# A7000RiscPC_Joystick.net
KiCad netlist of a schematic drawn in Altium Designer
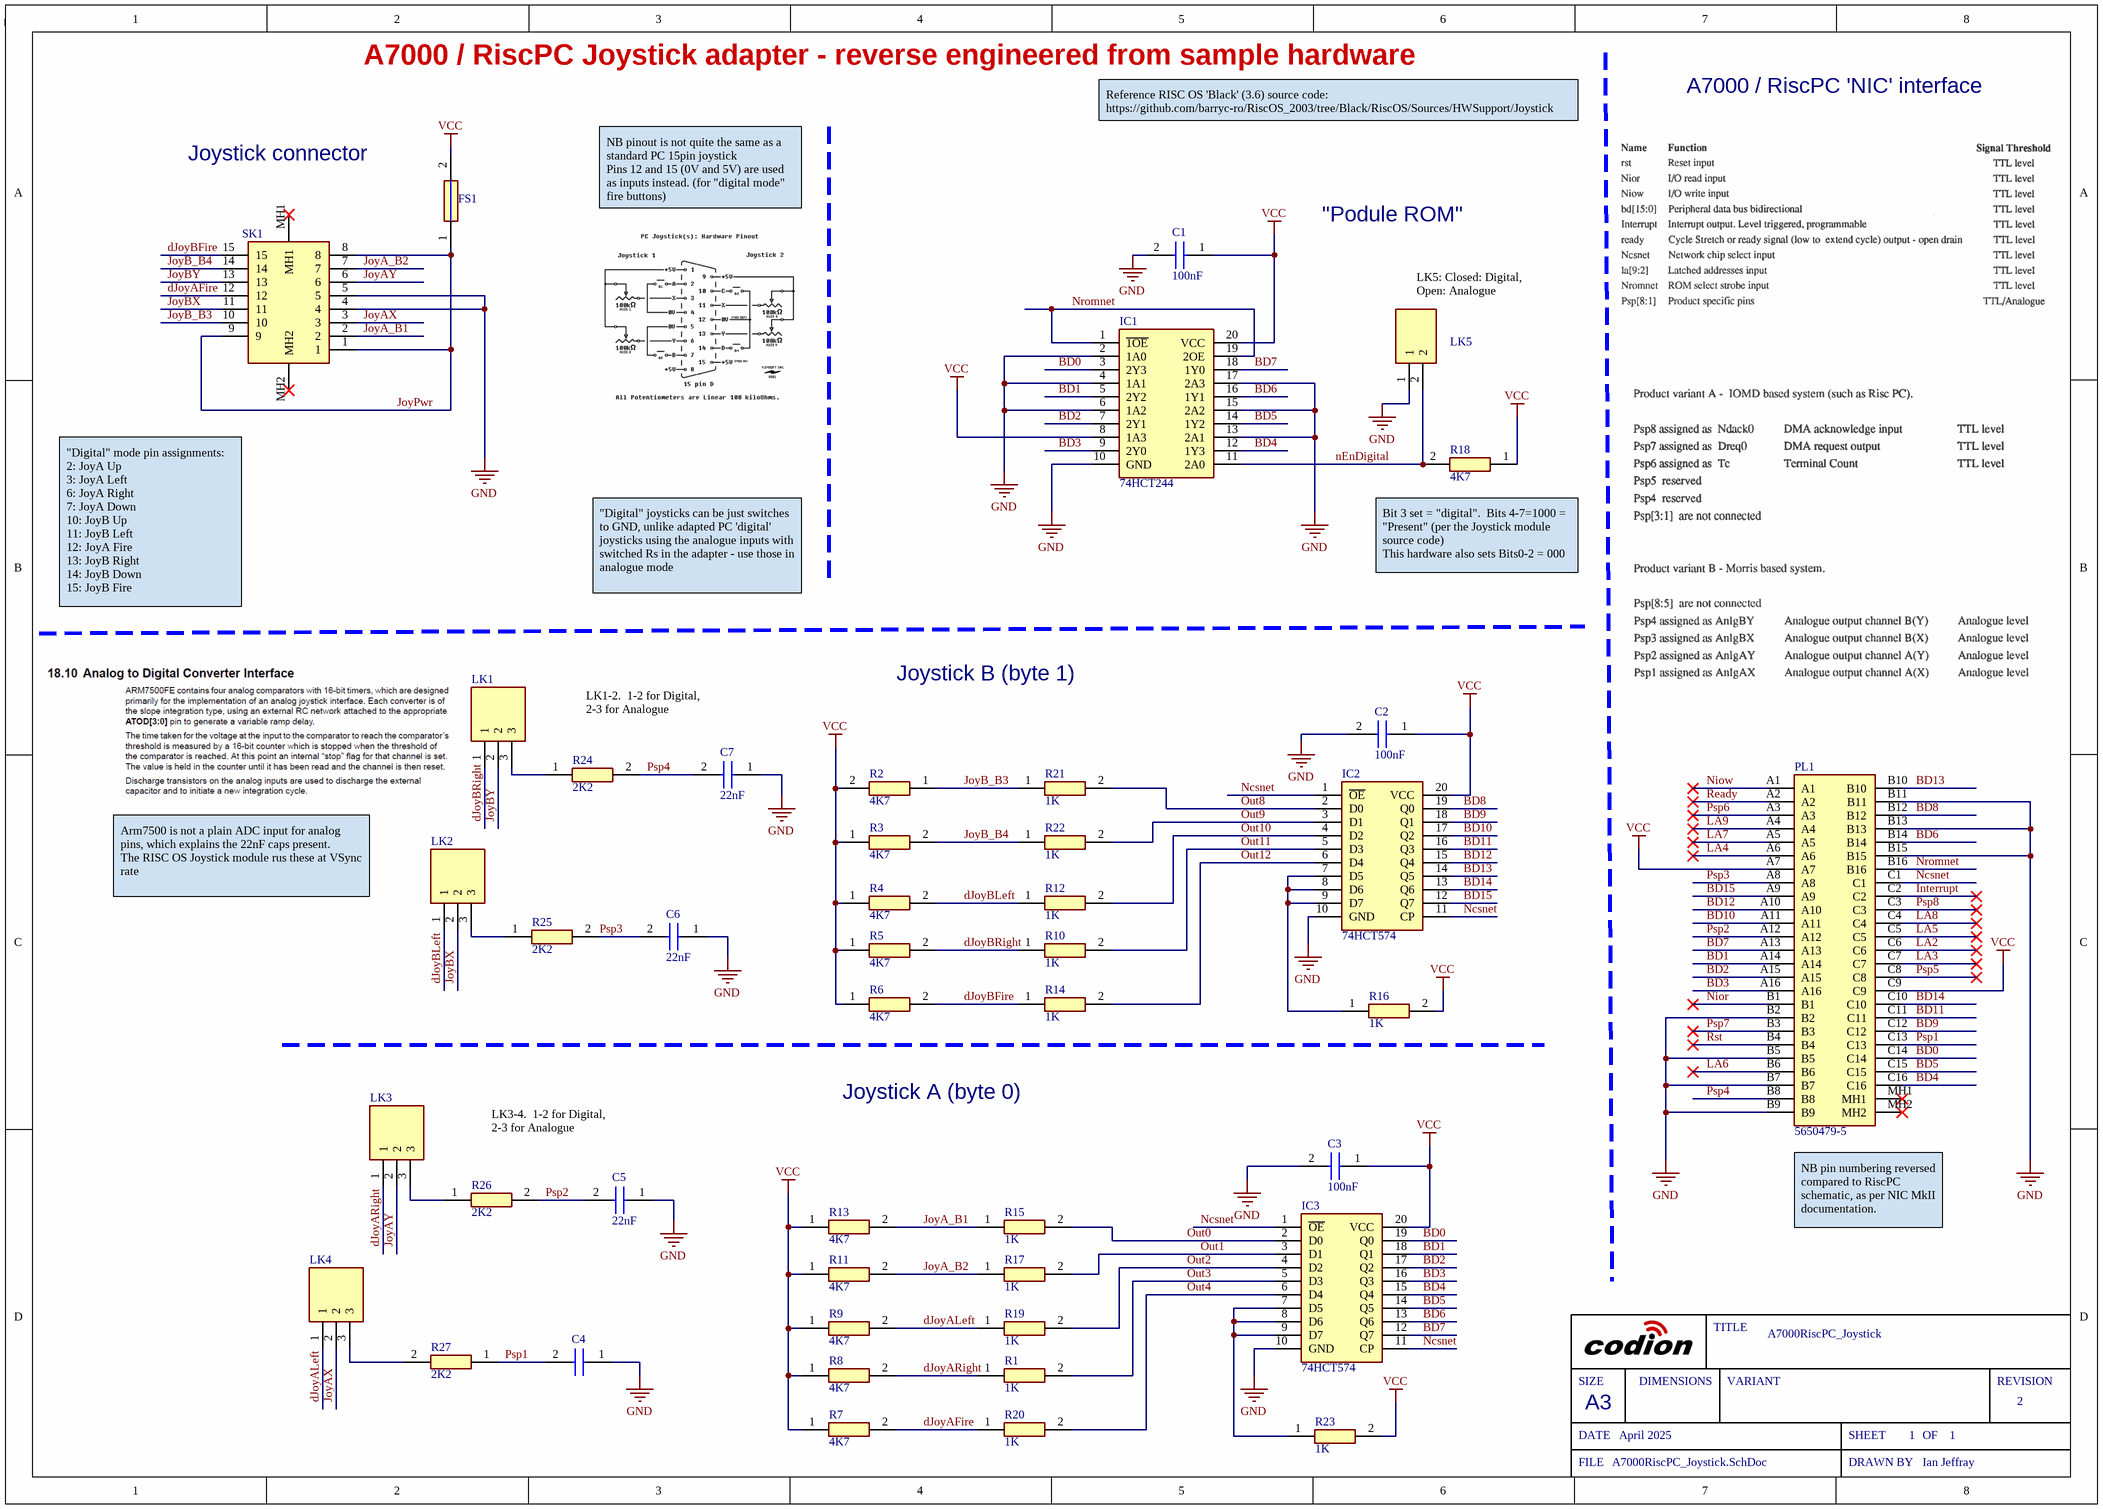
[diagram p0: A7000RiscPC_Joystick.SchDoc]

(export (version "E")
  (design (tool "Eeschema 10.0.6"))
  (components
    (comp (ref "C1")
      (value "100nF")
      (footprint "SamacSys:CAPC1608X90N")
      (description "Capacitor")
      (fields
        (field (name "MANUFACTURER_PART_NUMBER") "06033C104KAT4A")
        (field (name "MOUSER PART NUMBER") "581-06033C104KAT4A")
      )
      (libsource (lib "SamacSys") (part "06033C104KAT4A"))
    )
    (comp (ref "C2")
      (value "100nF")
      (footprint "SamacSys:CAPC1608X90N")
      (description "Capacitor")
      (fields
        (field (name "MANUFACTURER_PART_NUMBER") "06033C104KAT4A")
        (field (name "MOUSER PART NUMBER") "581-06033C104KAT4A")
      )
      (libsource (lib "SamacSys") (part "06033C104KAT4A"))
    )
    (comp (ref "C3")
      (value "100nF")
      (footprint "SamacSys:CAPC1608X90N")
      (description "Capacitor")
      (fields
        (field (name "MANUFACTURER_PART_NUMBER") "06033C104KAT4A")
        (field (name "MOUSER PART NUMBER") "581-06033C104KAT4A")
      )
      (libsource (lib "SamacSys") (part "06033C104KAT4A"))
    )
    (comp (ref "C4")
      (value "06033C104KAT4A")
      (footprint "SamacSys:CAPC1608X90N")
      (description "Capacitor")
      (fields (field (name "MOUSER PART NUMBER") "581-06033C104KAT4A"))
      (libsource (lib "SamacSys") (part "06033C104KAT4A"))
    )
    (comp (ref "C5")
      (value "22nF")
      (footprint "SamacSys:CAPC1608X90N")
      (description "Capacitor")
      (fields
        (field (name "MANUFACTURER_PART_NUMBER") "06035C223JAT2A")
        (field (name "MOUSER PART NUMBER") "581-06035C223JAT2A")
      )
      (libsource (lib "*") (part "06035C223JAT2A"))
    )
    (comp (ref "C6")
      (value "22nF")
      (footprint "SamacSys:CAPC1608X90N")
      (description "Capacitor")
      (fields
        (field (name "MANUFACTURER_PART_NUMBER") "06035C223JAT2A")
        (field (name "MOUSER PART NUMBER") "581-06035C223JAT2A")
      )
      (libsource (lib "*") (part "06035C223JAT2A"))
    )
    (comp (ref "C7")
      (value "22nF")
      (footprint "SamacSys:CAPC1608X90N")
      (description "Capacitor")
      (fields
        (field (name "MANUFACTURER_PART_NUMBER") "06035C223JAT2A")
        (field (name "MOUSER PART NUMBER") "581-06035C223JAT2A")
      )
      (libsource (lib "*") (part "06035C223JAT2A"))
    )
    (comp (ref "FS1")
      (value "0679L0250-05")
      (footprint "SamacSys:FUSC6125X279N")
      (description "Fuse")
      (fields (field (name "MOUSER PART NUMBER") "530-0679L0250-05"))
      (libsource (lib "*") (part "0679L0250-05"))
    )
    (comp (ref "IC1")
      (value "74HCT244")
      (footprint "SamacSys:SOIC127P1030X265-20N")
      (description "Integrated Circuit")
      (fields
        (field (name "MANUFACTURER_PART_NUMBER") "CD74HCT244M")
        (field (name "MOUSER PART NUMBER") "595-CD74HCT244M")
      )
      (libsource (lib "*") (part "CD74HCT244M"))
    )
    (comp (ref "IC2")
      (value "74HCT574")
      (footprint "SamacSys:SOIC127P1030X265-20N")
      (description "Integrated Circuit")
      (fields
        (field (name "MANUFACTURER_PART_NUMBER") "CD74HCT574M")
        (field (name "MOUSER PART NUMBER") "595-CD74HCT574M")
      )
      (libsource (lib "*") (part "CD74HCT574M"))
    )
    (comp (ref "IC3")
      (value "74HCT574")
      (footprint "SamacSys:SOIC127P1030X265-20N")
      (description "Integrated Circuit")
      (fields
        (field (name "MANUFACTURER_PART_NUMBER") "CD74HCT574M")
        (field (name "MOUSER PART NUMBER") "595-CD74HCT574M")
      )
      (libsource (lib "*") (part "CD74HCT574M"))
    )
    (comp (ref "LK1")
      (value "PREC003SAAN-RC")
      (footprint "SamacSys:HDRV3W64P0X254_1X3_762X254X868P")
      (description "Connector")
      (libsource (lib "*") (part "PREC003SAAN-RC"))
    )
    (comp (ref "LK2")
      (value "PREC003SAAN-RC")
      (footprint "SamacSys:HDRV3W64P0X254_1X3_762X254X868P")
      (description "Connector")
      (libsource (lib "*") (part "PREC003SAAN-RC"))
    )
    (comp (ref "LK3")
      (value "PREC003SAAN-RC")
      (footprint "SamacSys:HDRV3W64P0X254_1X3_762X254X868P")
      (description "Connector")
      (libsource (lib "*") (part "PREC003SAAN-RC"))
    )
    (comp (ref "LK4")
      (value "PREC003SAAN-RC")
      (footprint "SamacSys:HDRV3W64P0X254_1X3_762X254X868P")
      (description "Connector")
      (libsource (lib "*") (part "PREC003SAAN-RC"))
    )
    (comp (ref "LK5")
      (value "PREC002SAAN-RC")
      (footprint "SamacSys:HDRV2W64P0X254_1X2_508X254X854P")
      (description "Connector")
      (libsource (lib "*") (part "PREC002SAAN-RC"))
    )
    (comp (ref "PL1")
      (value "5650479-5")
      (footprint "SamacSys:56504795")
      (description "Connector")
      (fields (field (name "MOUSER PART NUMBER") "571-5650479-5"))
      (libsource (lib "*") (part "5650479-5"))
    )
    (comp (ref "R1")
      (value "1K")
      (footprint "SamacSys:RESC1005X35N")
      (description "Resistor")
      (fields
        (field (name "MANUFACTURER_PART_NUMBER") "CPF0402B102KE1")
        (field (name "MOUSER PART NUMBER") "279-CPF0402B102KE1")
      )
      (libsource (lib "*") (part "CPF0402B102KE1"))
    )
    (comp (ref "R2")
      (value "4K7")
      (footprint "SamacSys:RESC1005X35N")
      (description "Resistor")
      (fields
        (field (name "MANUFACTURER_PART_NUMBER") "CPF0402B4K7E")
        (field (name "MOUSER PART NUMBER") "279-CPF0402B4K7E")
      )
      (libsource (lib "") (part "CPF0402B4K7E_1"))
    )
    (comp (ref "R3")
      (value "4K7")
      (footprint "SamacSys:RESC1005X35N")
      (description "Resistor")
      (fields
        (field (name "MANUFACTURER_PART_NUMBER") "CPF0402B4K7E")
        (field (name "MOUSER PART NUMBER") "279-CPF0402B4K7E")
      )
      (libsource (lib "*") (part "CPF0402B4K7E"))
    )
    (comp (ref "R4")
      (value "4K7")
      (footprint "SamacSys:RESC1005X35N")
      (description "Resistor")
      (fields
        (field (name "MANUFACTURER_PART_NUMBER") "CPF0402B4K7E")
        (field (name "MOUSER PART NUMBER") "279-CPF0402B4K7E")
      )
      (libsource (lib "*") (part "CPF0402B4K7E"))
    )
    (comp (ref "R5")
      (value "4K7")
      (footprint "SamacSys:RESC1005X35N")
      (description "Resistor")
      (fields
        (field (name "MANUFACTURER_PART_NUMBER") "CPF0402B4K7E")
        (field (name "MOUSER PART NUMBER") "279-CPF0402B4K7E")
      )
      (libsource (lib "*") (part "CPF0402B4K7E"))
    )
    (comp (ref "R6")
      (value "4K7")
      (footprint "SamacSys:RESC1005X35N")
      (description "Resistor")
      (fields
        (field (name "MANUFACTURER_PART_NUMBER") "CPF0402B4K7E")
        (field (name "MOUSER PART NUMBER") "279-CPF0402B4K7E")
      )
      (libsource (lib "*") (part "CPF0402B4K7E"))
    )
    (comp (ref "R7")
      (value "4K7")
      (footprint "SamacSys:RESC1005X35N")
      (description "Resistor")
      (fields
        (field (name "MANUFACTURER_PART_NUMBER") "CPF0402B4K7E")
        (field (name "MOUSER PART NUMBER") "279-CPF0402B4K7E")
      )
      (libsource (lib "*") (part "CPF0402B4K7E"))
    )
    (comp (ref "R8")
      (value "4K7")
      (footprint "SamacSys:RESC1005X35N")
      (description "Resistor")
      (fields
        (field (name "MANUFACTURER_PART_NUMBER") "CPF0402B4K7E")
        (field (name "MOUSER PART NUMBER") "279-CPF0402B4K7E")
      )
      (libsource (lib "*") (part "CPF0402B4K7E"))
    )
    (comp (ref "R9")
      (value "4K7")
      (footprint "SamacSys:RESC1005X35N")
      (description "Resistor")
      (fields
        (field (name "MANUFACTURER_PART_NUMBER") "CPF0402B4K7E")
        (field (name "MOUSER PART NUMBER") "279-CPF0402B4K7E")
      )
      (libsource (lib "*") (part "CPF0402B4K7E"))
    )
    (comp (ref "R10")
      (value "1K")
      (footprint "SamacSys:RESC1005X35N")
      (description "Resistor")
      (fields
        (field (name "MANUFACTURER_PART_NUMBER") "CPF0402B102KE1")
        (field (name "MOUSER PART NUMBER") "279-CPF0402B102KE1")
      )
      (libsource (lib "*") (part "CPF0402B102KE1"))
    )
    (comp (ref "R11")
      (value "4K7")
      (footprint "SamacSys:RESC1005X35N")
      (description "Resistor")
      (fields
        (field (name "MANUFACTURER_PART_NUMBER") "CPF0402B4K7E")
        (field (name "MOUSER PART NUMBER") "279-CPF0402B4K7E")
      )
      (libsource (lib "*") (part "CPF0402B4K7E"))
    )
    (comp (ref "R12")
      (value "1K")
      (footprint "SamacSys:RESC1005X35N")
      (description "Resistor")
      (fields
        (field (name "MANUFACTURER_PART_NUMBER") "CPF0402B102KE1")
        (field (name "MOUSER PART NUMBER") "279-CPF0402B102KE1")
      )
      (libsource (lib "*") (part "CPF0402B102KE1"))
    )
    (comp (ref "R13")
      (value "4K7")
      (footprint "SamacSys:RESC1005X35N")
      (description "Resistor")
      (fields
        (field (name "MANUFACTURER_PART_NUMBER") "CPF0402B4K7E")
        (field (name "MOUSER PART NUMBER") "279-CPF0402B4K7E")
      )
      (libsource (lib "*") (part "CPF0402B4K7E"))
    )
    (comp (ref "R14")
      (value "1K")
      (footprint "SamacSys:RESC1005X35N")
      (description "Resistor")
      (fields
        (field (name "MANUFACTURER_PART_NUMBER") "CPF0402B102KE1")
        (field (name "MOUSER PART NUMBER") "279-CPF0402B102KE1")
      )
      (libsource (lib "*") (part "CPF0402B102KE1"))
    )
    (comp (ref "R15")
      (value "1K")
      (footprint "SamacSys:RESC1005X35N")
      (description "Resistor")
      (fields
        (field (name "MANUFACTURER_PART_NUMBER") "CPF0402B102KE1")
        (field (name "MOUSER PART NUMBER") "279-CPF0402B102KE1")
      )
      (libsource (lib "*") (part "CPF0402B102KE1"))
    )
    (comp (ref "R16")
      (value "1K")
      (footprint "SamacSys:RESC1005X35N")
      (description "Resistor")
      (fields (field (name "MANUFACTURER_PART_NUMBER") "CPF0402B2K2E"))
      (libsource (lib "") (part "CPF0402B2K2E_1"))
    )
    (comp (ref "R17")
      (value "1K")
      (footprint "SamacSys:RESC1005X35N")
      (description "Resistor")
      (fields
        (field (name "MANUFACTURER_PART_NUMBER") "CPF0402B102KE1")
        (field (name "MOUSER PART NUMBER") "279-CPF0402B102KE1")
      )
      (libsource (lib "*") (part "CPF0402B102KE1"))
    )
    (comp (ref "R18")
      (value "4K7")
      (footprint "SamacSys:RESC1005X35N")
      (description "Resistor")
      (fields
        (field (name "MANUFACTURER_PART_NUMBER") "CPF0402B4K7E")
        (field (name "MOUSER PART NUMBER") "279-CPF0402B4K7E")
      )
      (libsource (lib "") (part "CPF0402B4K7E_1"))
    )
    (comp (ref "R19")
      (value "1K")
      (footprint "SamacSys:RESC1005X35N")
      (description "Resistor")
      (fields
        (field (name "MANUFACTURER_PART_NUMBER") "CPF0402B102KE1")
        (field (name "MOUSER PART NUMBER") "279-CPF0402B102KE1")
      )
      (libsource (lib "*") (part "CPF0402B102KE1"))
    )
    (comp (ref "R20")
      (value "1K")
      (footprint "SamacSys:RESC1005X35N")
      (description "Resistor")
      (fields
        (field (name "MANUFACTURER_PART_NUMBER") "CPF0402B102KE1")
        (field (name "MOUSER PART NUMBER") "279-CPF0402B102KE1")
      )
      (libsource (lib "*") (part "CPF0402B102KE1"))
    )
    (comp (ref "R21")
      (value "1K")
      (footprint "SamacSys:RESC1005X35N")
      (description "Resistor")
      (fields
        (field (name "MANUFACTURER_PART_NUMBER") "CPF0402B102KE1")
        (field (name "MOUSER PART NUMBER") "279-CPF0402B102KE1")
      )
      (libsource (lib "*") (part "CPF0402B102KE1"))
    )
    (comp (ref "R22")
      (value "1K")
      (footprint "SamacSys:RESC1005X35N")
      (description "Resistor")
      (fields
        (field (name "MANUFACTURER_PART_NUMBER") "CPF0402B102KE1")
        (field (name "MOUSER PART NUMBER") "279-CPF0402B102KE1")
      )
      (libsource (lib "*") (part "CPF0402B102KE1"))
    )
    (comp (ref "R23")
      (value "1K")
      (footprint "SamacSys:RESC1005X35N")
      (description "Resistor")
      (fields
        (field (name "MANUFACTURER_PART_NUMBER") "CPF0402B102KE1")
        (field (name "MOUSER PART NUMBER") "279-CPF0402B102KE1")
      )
      (libsource (lib "*") (part "CPF0402B102KE1"))
    )
    (comp (ref "R24")
      (value "2K2")
      (footprint "SamacSys:RESC1005X35N")
      (description "Resistor")
      (fields (field (name "MANUFACTURER_PART_NUMBER") "CPF0402B2K2E"))
      (libsource (lib "") (part "CPF0402B2K2E_1"))
    )
    (comp (ref "R25")
      (value "2K2")
      (footprint "SamacSys:RESC1005X35N")
      (description "Resistor")
      (fields (field (name "MANUFACTURER_PART_NUMBER") "CPF0402B2K2E"))
      (libsource (lib "") (part "CPF0402B2K2E_1"))
    )
    (comp (ref "R26")
      (value "2K2")
      (footprint "SamacSys:RESC1005X35N")
      (description "Resistor")
      (fields (field (name "MANUFACTURER_PART_NUMBER") "CPF0402B2K2E"))
      (libsource (lib "") (part "CPF0402B2K2E_1"))
    )
    (comp (ref "R27")
      (value "2K2")
      (footprint "SamacSys:RESC1005X35N")
      (description "Resistor")
      (fields (field (name "MANUFACTURER_PART_NUMBER") "CPF0402B2K2E"))
      (libsource (lib "*") (part "CPF0402B2K2E"))
    )
    (comp (ref "SK1")
      (value "5747845-4")
      (footprint "SamacSys:57478454")
      (description "Connector")
      (fields (field (name "MOUSER PART NUMBER") "571-5747845-4"))
      (libsource (lib "*") (part "5747845-4"))
    )
  )
  (nets
    (net (code "1") (name "/BD0") (class "Default")
      (node (ref "IC1") (pin "3") (pinfunction "2Y3_3") (pintype "passive"))
      (node (ref "IC3") (pin "19") (pinfunction "Q0_19") (pintype "passive"))
      (node (ref "PL1") (pin "C14") (pinfunction "C14_C14") (pintype "passive"))
    )
    (net (code "2") (name "/BD1") (class "Default")
      (node (ref "IC1") (pin "5") (pinfunction "2Y2_5") (pintype "passive"))
      (node (ref "IC3") (pin "18") (pinfunction "Q1_18") (pintype "passive"))
      (node (ref "PL1") (pin "A14") (pinfunction "A14_A14") (pintype "passive"))
    )
    (net (code "3") (name "/BD2") (class "Default")
      (node (ref "IC1") (pin "7") (pinfunction "2Y1_7") (pintype "passive"))
      (node (ref "IC3") (pin "17") (pinfunction "Q2_17") (pintype "passive"))
      (node (ref "PL1") (pin "A15") (pinfunction "A15_A15") (pintype "passive"))
    )
    (net (code "4") (name "/BD3") (class "Default")
      (node (ref "IC1") (pin "9") (pinfunction "2Y0_9") (pintype "passive"))
      (node (ref "IC3") (pin "16") (pinfunction "Q3_16") (pintype "passive"))
      (node (ref "PL1") (pin "A16") (pinfunction "A16_A16") (pintype "passive"))
    )
    (net (code "5") (name "/BD4") (class "Default")
      (node (ref "IC1") (pin "12") (pinfunction "1Y3_12") (pintype "passive"))
      (node (ref "IC3") (pin "15") (pinfunction "Q4_15") (pintype "passive"))
      (node (ref "PL1") (pin "C16") (pinfunction "C16_C16") (pintype "passive"))
    )
    (net (code "6") (name "/BD5") (class "Default")
      (node (ref "IC1") (pin "14") (pinfunction "1Y2_14") (pintype "passive"))
      (node (ref "IC3") (pin "14") (pinfunction "Q5_14") (pintype "passive"))
      (node (ref "PL1") (pin "C15") (pinfunction "C15_C15") (pintype "passive"))
    )
    (net (code "7") (name "/BD6") (class "Default")
      (node (ref "IC1") (pin "16") (pinfunction "1Y1_16") (pintype "passive"))
      (node (ref "IC3") (pin "13") (pinfunction "Q6_13") (pintype "passive"))
      (node (ref "PL1") (pin "B14") (pinfunction "B14_B14") (pintype "passive"))
    )
    (net (code "8") (name "/BD7") (class "Default")
      (node (ref "IC1") (pin "18") (pinfunction "1Y0_18") (pintype "passive"))
      (node (ref "IC3") (pin "12") (pinfunction "Q7_12") (pintype "passive"))
      (node (ref "PL1") (pin "A13") (pinfunction "A13_A13") (pintype "passive"))
    )
    (net (code "9") (name "/BD8") (class "Default")
      (node (ref "IC2") (pin "19") (pinfunction "Q0_19") (pintype "passive"))
      (node (ref "PL1") (pin "B12") (pinfunction "B12_B12") (pintype "passive"))
    )
    (net (code "10") (name "/BD9") (class "Default")
      (node (ref "IC2") (pin "18") (pinfunction "Q1_18") (pintype "passive"))
      (node (ref "PL1") (pin "C12") (pinfunction "C12_C12") (pintype "passive"))
    )
    (net (code "11") (name "/BD10") (class "Default")
      (node (ref "IC2") (pin "17") (pinfunction "Q2_17") (pintype "passive"))
      (node (ref "PL1") (pin "A11") (pinfunction "A11_A11") (pintype "passive"))
    )
    (net (code "12") (name "/BD11") (class "Default")
      (node (ref "IC2") (pin "16") (pinfunction "Q3_16") (pintype "passive"))
      (node (ref "PL1") (pin "C11") (pinfunction "C11_C11") (pintype "passive"))
    )
    (net (code "13") (name "/BD12") (class "Default")
      (node (ref "IC2") (pin "15") (pinfunction "Q4_15") (pintype "passive"))
      (node (ref "PL1") (pin "A10") (pinfunction "A10_A10") (pintype "passive"))
    )
    (net (code "14") (name "/BD13") (class "Default")
      (node (ref "IC2") (pin "14") (pinfunction "Q5_14") (pintype "passive"))
      (node (ref "PL1") (pin "B10") (pinfunction "B10_B10") (pintype "passive"))
    )
    (net (code "15") (name "/BD14") (class "Default")
      (node (ref "IC2") (pin "13") (pinfunction "Q6_13") (pintype "passive"))
      (node (ref "PL1") (pin "C10") (pinfunction "C10_C10") (pintype "passive"))
    )
    (net (code "16") (name "/BD15") (class "Default")
      (node (ref "IC2") (pin "12") (pinfunction "Q7_12") (pintype "passive"))
      (node (ref "PL1") (pin "A9") (pinfunction "A9_A9") (pintype "passive"))
    )
    (net (code "17") (name "/Interrupt") (class "Default")
      (node (ref "PL1") (pin "C2") (pinfunction "C2_C2") (pintype "passive+no_connect"))
    )
    (net (code "18") (name "/JoyAX") (class "Default")
      (node (ref "LK4") (pin "2") (pinfunction "2_2") (pintype "passive"))
      (node (ref "SK1") (pin "3") (pinfunction "3_3") (pintype "passive"))
    )
    (net (code "19") (name "/JoyAY") (class "Default")
      (node (ref "LK3") (pin "2") (pinfunction "2_2") (pintype "passive"))
      (node (ref "SK1") (pin "6") (pinfunction "6_6") (pintype "passive"))
    )
    (net (code "20") (name "/JoyA_B1") (class "Default")
      (node (ref "R13") (pin "2") (pinfunction "2_2") (pintype "passive"))
      (node (ref "R15") (pin "1") (pinfunction "1_1") (pintype "passive"))
      (node (ref "SK1") (pin "2") (pinfunction "2_2") (pintype "passive"))
    )
    (net (code "21") (name "/JoyA_B2") (class "Default")
      (node (ref "R11") (pin "2") (pinfunction "2_2") (pintype "passive"))
      (node (ref "R17") (pin "1") (pinfunction "1_1") (pintype "passive"))
      (node (ref "SK1") (pin "7") (pinfunction "7_7") (pintype "passive"))
    )
    (net (code "22") (name "/JoyBX") (class "Default")
      (node (ref "LK2") (pin "2") (pinfunction "2_2") (pintype "passive"))
      (node (ref "SK1") (pin "11") (pinfunction "11_11") (pintype "passive"))
    )
    (net (code "23") (name "/JoyBY") (class "Default")
      (node (ref "LK1") (pin "2") (pinfunction "2_2") (pintype "passive"))
      (node (ref "SK1") (pin "13") (pinfunction "13_13") (pintype "passive"))
    )
    (net (code "24") (name "/JoyB_B3") (class "Default")
      (node (ref "R2") (pin "1") (pinfunction "1_1") (pintype "passive"))
      (node (ref "R21") (pin "1") (pinfunction "1_1") (pintype "passive"))
      (node (ref "SK1") (pin "10") (pinfunction "10_10") (pintype "passive"))
    )
    (net (code "25") (name "/JoyB_B4") (class "Default")
      (node (ref "R22") (pin "1") (pinfunction "1_1") (pintype "passive"))
      (node (ref "R3") (pin "2") (pinfunction "2_2") (pintype "passive"))
      (node (ref "SK1") (pin "14") (pinfunction "14_14") (pintype "passive"))
    )
    (net (code "26") (name "/JoyPwr") (class "Default")
      (node (ref "FS1") (pin "1") (pinfunction "1_1") (pintype "passive"))
      (node (ref "SK1") (pin "1") (pinfunction "1_1") (pintype "passive"))
      (node (ref "SK1") (pin "8") (pinfunction "8_8") (pintype "passive"))
      (node (ref "SK1") (pin "9") (pinfunction "9_9") (pintype "passive"))
    )
    (net (code "27") (name "/LA2") (class "Default")
      (node (ref "PL1") (pin "C6") (pinfunction "C6_C6") (pintype "passive+no_connect"))
    )
    (net (code "28") (name "/LA3") (class "Default")
      (node (ref "PL1") (pin "C7") (pinfunction "C7_C7") (pintype "passive+no_connect"))
    )
    (net (code "29") (name "/LA4") (class "Default")
      (node (ref "PL1") (pin "A6") (pinfunction "A6_A6") (pintype "passive+no_connect"))
    )
    (net (code "30") (name "/LA5") (class "Default")
      (node (ref "PL1") (pin "C5") (pinfunction "C5_C5") (pintype "passive+no_connect"))
    )
    (net (code "31") (name "/LA6") (class "Default")
      (node (ref "PL1") (pin "B6") (pinfunction "B6_B6") (pintype "passive+no_connect"))
    )
    (net (code "32") (name "/LA7") (class "Default")
      (node (ref "PL1") (pin "A5") (pinfunction "A5_A5") (pintype "passive+no_connect"))
    )
    (net (code "33") (name "/LA8") (class "Default")
      (node (ref "PL1") (pin "C4") (pinfunction "C4_C4") (pintype "passive+no_connect"))
    )
    (net (code "34") (name "/LA9") (class "Default")
      (node (ref "PL1") (pin "A4") (pinfunction "A4_A4") (pintype "passive+no_connect"))
    )
    (net (code "35") (name "/Ncsnet") (class "Default")
      (node (ref "IC2") (pin "1") (pinfunction "~{OE}_1") (pintype "passive"))
      (node (ref "IC2") (pin "11") (pinfunction "CP_11") (pintype "passive"))
      (node (ref "IC3") (pin "1") (pinfunction "~{OE}_1") (pintype "passive"))
      (node (ref "IC3") (pin "11") (pinfunction "CP_11") (pintype "passive"))
      (node (ref "PL1") (pin "C1") (pinfunction "C1_C1") (pintype "passive"))
    )
    (net (code "36") (name "/Nior") (class "Default")
      (node (ref "PL1") (pin "B1") (pinfunction "B1_B1") (pintype "passive+no_connect"))
    )
    (net (code "37") (name "/Niow") (class "Default")
      (node (ref "PL1") (pin "A1") (pinfunction "A1_A1") (pintype "passive+no_connect"))
    )
    (net (code "38") (name "/Nromnet") (class "Default")
      (node (ref "IC1") (pin "1") (pinfunction "~{1OE}_1") (pintype "passive"))
      (node (ref "IC1") (pin "19") (pinfunction "2OE_19") (pintype "passive"))
      (node (ref "PL1") (pin "B16") (pinfunction "B16_B16") (pintype "passive"))
    )
    (net (code "39") (name "/Out0") (class "Default")
      (node (ref "IC3") (pin "2") (pinfunction "D0_2") (pintype "passive"))
      (node (ref "R15") (pin "2") (pinfunction "2_2") (pintype "passive"))
    )
    (net (code "40") (name "/Out1") (class "Default")
      (node (ref "IC3") (pin "3") (pinfunction "D1_3") (pintype "passive"))
      (node (ref "R17") (pin "2") (pinfunction "2_2") (pintype "passive"))
    )
    (net (code "41") (name "/Out2") (class "Default")
      (node (ref "IC3") (pin "4") (pinfunction "D2_4") (pintype "passive"))
      (node (ref "R19") (pin "2") (pinfunction "2_2") (pintype "passive"))
    )
    (net (code "42") (name "/Out3") (class "Default")
      (node (ref "IC3") (pin "5") (pinfunction "D3_5") (pintype "passive"))
      (node (ref "R1") (pin "2") (pinfunction "2_2") (pintype "passive"))
    )
    (net (code "43") (name "/Out4") (class "Default")
      (node (ref "IC3") (pin "6") (pinfunction "D4_6") (pintype "passive"))
      (node (ref "R20") (pin "2") (pinfunction "2_2") (pintype "passive"))
    )
    (net (code "44") (name "/Out8") (class "Default")
      (node (ref "IC2") (pin "2") (pinfunction "D0_2") (pintype "passive"))
      (node (ref "R21") (pin "2") (pinfunction "2_2") (pintype "passive"))
    )
    (net (code "45") (name "/Out9") (class "Default")
      (node (ref "IC2") (pin "3") (pinfunction "D1_3") (pintype "passive"))
      (node (ref "R22") (pin "2") (pinfunction "2_2") (pintype "passive"))
    )
    (net (code "46") (name "/Out10") (class "Default")
      (node (ref "IC2") (pin "4") (pinfunction "D2_4") (pintype "passive"))
      (node (ref "R12") (pin "2") (pinfunction "2_2") (pintype "passive"))
    )
    (net (code "47") (name "/Out11") (class "Default")
      (node (ref "IC2") (pin "5") (pinfunction "D3_5") (pintype "passive"))
      (node (ref "R10") (pin "2") (pinfunction "2_2") (pintype "passive"))
    )
    (net (code "48") (name "/Out12") (class "Default")
      (node (ref "IC2") (pin "6") (pinfunction "D4_6") (pintype "passive"))
      (node (ref "R14") (pin "2") (pinfunction "2_2") (pintype "passive"))
    )
    (net (code "49") (name "/Psp1") (class "Default")
      (node (ref "C4") (pin "2") (pinfunction "2_2") (pintype "passive"))
      (node (ref "PL1") (pin "C13") (pinfunction "C13_C13") (pintype "passive"))
      (node (ref "R27") (pin "1") (pinfunction "1_1") (pintype "passive"))
    )
    (net (code "50") (name "/Psp2") (class "Default")
      (node (ref "C5") (pin "2") (pinfunction "2_2") (pintype "passive"))
      (node (ref "PL1") (pin "A12") (pinfunction "A12_A12") (pintype "passive"))
      (node (ref "R26") (pin "2") (pinfunction "2_2") (pintype "passive"))
    )
    (net (code "51") (name "/Psp3") (class "Default")
      (node (ref "C6") (pin "2") (pinfunction "2_2") (pintype "passive"))
      (node (ref "PL1") (pin "A8") (pinfunction "A8_A8") (pintype "passive"))
      (node (ref "R25") (pin "2") (pinfunction "2_2") (pintype "passive"))
    )
    (net (code "52") (name "/Psp4") (class "Default")
      (node (ref "C7") (pin "2") (pinfunction "2_2") (pintype "passive"))
      (node (ref "PL1") (pin "B8") (pinfunction "B8_B8") (pintype "passive"))
      (node (ref "R24") (pin "2") (pinfunction "2_2") (pintype "passive"))
    )
    (net (code "53") (name "/Psp5") (class "Default")
      (node (ref "PL1") (pin "C8") (pinfunction "C8_C8") (pintype "passive+no_connect"))
    )
    (net (code "54") (name "/Psp6") (class "Default")
      (node (ref "PL1") (pin "A3") (pinfunction "A3_A3") (pintype "passive+no_connect"))
    )
    (net (code "55") (name "/Psp7") (class "Default")
      (node (ref "PL1") (pin "B3") (pinfunction "B3_B3") (pintype "passive+no_connect"))
    )
    (net (code "56") (name "/Psp8") (class "Default")
      (node (ref "PL1") (pin "C3") (pinfunction "C3_C3") (pintype "passive+no_connect"))
    )
    (net (code "57") (name "/Ready") (class "Default")
      (node (ref "PL1") (pin "A2") (pinfunction "A2_A2") (pintype "passive+no_connect"))
    )
    (net (code "58") (name "/Rst") (class "Default")
      (node (ref "PL1") (pin "B4") (pinfunction "B4_B4") (pintype "passive+no_connect"))
    )
    (net (code "59") (name "/dJoyAFire") (class "Default")
      (node (ref "R20") (pin "1") (pinfunction "1_1") (pintype "passive"))
      (node (ref "R7") (pin "2") (pinfunction "2_2") (pintype "passive"))
      (node (ref "SK1") (pin "12") (pinfunction "12_12") (pintype "passive"))
    )
    (net (code "60") (name "/dJoyALeft") (class "Default")
      (node (ref "LK4") (pin "1") (pinfunction "1_1") (pintype "passive"))
      (node (ref "R19") (pin "1") (pinfunction "1_1") (pintype "passive"))
      (node (ref "R9") (pin "2") (pinfunction "2_2") (pintype "passive"))
    )
    (net (code "61") (name "/dJoyARight") (class "Default")
      (node (ref "LK3") (pin "1") (pinfunction "1_1") (pintype "passive"))
      (node (ref "R1") (pin "1") (pinfunction "1_1") (pintype "passive"))
      (node (ref "R8") (pin "2") (pinfunction "2_2") (pintype "passive"))
    )
    (net (code "62") (name "/dJoyBFire") (class "Default")
      (node (ref "R14") (pin "1") (pinfunction "1_1") (pintype "passive"))
      (node (ref "R6") (pin "2") (pinfunction "2_2") (pintype "passive"))
      (node (ref "SK1") (pin "15") (pinfunction "15_15") (pintype "passive"))
    )
    (net (code "63") (name "/dJoyBLeft") (class "Default")
      (node (ref "LK2") (pin "1") (pinfunction "1_1") (pintype "passive"))
      (node (ref "R12") (pin "1") (pinfunction "1_1") (pintype "passive"))
      (node (ref "R4") (pin "2") (pinfunction "2_2") (pintype "passive"))
    )
    (net (code "64") (name "/dJoyBRight") (class "Default")
      (node (ref "LK1") (pin "1") (pinfunction "1_1") (pintype "passive"))
      (node (ref "R10") (pin "1") (pinfunction "1_1") (pintype "passive"))
      (node (ref "R5") (pin "2") (pinfunction "2_2") (pintype "passive"))
    )
    (net (code "65") (name "/nEnDigital") (class "Default")
      (node (ref "IC1") (pin "11") (pinfunction "2A0_11") (pintype "passive"))
      (node (ref "LK5") (pin "2") (pinfunction "2_2") (pintype "passive"))
      (node (ref "R18") (pin "2") (pinfunction "2_2") (pintype "passive"))
    )
    (net (code "66") (name "GND") (class "Default")
      (node (ref "C1") (pin "2") (pinfunction "2_2") (pintype "passive"))
      (node (ref "C2") (pin "2") (pinfunction "2_2") (pintype "passive"))
      (node (ref "C3") (pin "2") (pinfunction "2_2") (pintype "passive"))
      (node (ref "C4") (pin "1") (pinfunction "1_1") (pintype "passive"))
      (node (ref "C5") (pin "1") (pinfunction "1_1") (pintype "passive"))
      (node (ref "C6") (pin "1") (pinfunction "1_1") (pintype "passive"))
      (node (ref "C7") (pin "1") (pinfunction "1_1") (pintype "passive"))
      (node (ref "IC1") (pin "10") (pinfunction "GND_10") (pintype "passive"))
      (node (ref "IC1") (pin "13") (pinfunction "2A1_13") (pintype "passive"))
      (node (ref "IC1") (pin "15") (pinfunction "2A2_15") (pintype "passive"))
      (node (ref "IC1") (pin "17") (pinfunction "2A3_17") (pintype "passive"))
      (node (ref "IC1") (pin "2") (pinfunction "1A0_2") (pintype "passive"))
      (node (ref "IC1") (pin "4") (pinfunction "1A1_4") (pintype "passive"))
      (node (ref "IC1") (pin "6") (pinfunction "1A2_6") (pintype "passive"))
      (node (ref "IC2") (pin "10") (pinfunction "GND_10") (pintype "passive"))
      (node (ref "IC3") (pin "10") (pinfunction "GND_10") (pintype "passive"))
      (node (ref "LK5") (pin "1") (pinfunction "1_1") (pintype "passive"))
      (node (ref "PL1") (pin "B11") (pinfunction "B11_B11") (pintype "passive"))
      (node (ref "PL1") (pin "B13") (pinfunction "B13_B13") (pintype "passive"))
      (node (ref "PL1") (pin "B15") (pinfunction "B15_B15") (pintype "passive"))
      (node (ref "PL1") (pin "B2") (pinfunction "B2_B2") (pintype "passive"))
      (node (ref "PL1") (pin "B5") (pinfunction "B5_B5") (pintype "passive"))
      (node (ref "PL1") (pin "B7") (pinfunction "B7_B7") (pintype "passive"))
      (node (ref "PL1") (pin "B9") (pinfunction "B9_B9") (pintype "passive"))
      (node (ref "SK1") (pin "4") (pinfunction "4_4") (pintype "passive"))
      (node (ref "SK1") (pin "5") (pinfunction "5_5") (pintype "passive"))
    )
    (net (code "67") (name "Net-(IC2-D5)") (class "Default")
      (node (ref "IC2") (pin "7") (pinfunction "D5_7") (pintype "passive"))
      (node (ref "IC2") (pin "8") (pinfunction "D6_8") (pintype "passive"))
      (node (ref "IC2") (pin "9") (pinfunction "D7_9") (pintype "passive"))
      (node (ref "R16") (pin "1") (pinfunction "1_1") (pintype "passive"))
    )
    (net (code "68") (name "Net-(IC3-D5)") (class "Default")
      (node (ref "IC3") (pin "7") (pinfunction "D5_7") (pintype "passive"))
      (node (ref "IC3") (pin "8") (pinfunction "D6_8") (pintype "passive"))
      (node (ref "IC3") (pin "9") (pinfunction "D7_9") (pintype "passive"))
      (node (ref "R23") (pin "1") (pinfunction "1_1") (pintype "passive"))
    )
    (net (code "69") (name "Net-(LK1-Pad3)") (class "Default")
      (node (ref "LK1") (pin "3") (pinfunction "3_3") (pintype "passive"))
      (node (ref "R24") (pin "1") (pinfunction "1_1") (pintype "passive"))
    )
    (net (code "70") (name "Net-(LK2-Pad3)") (class "Default")
      (node (ref "LK2") (pin "3") (pinfunction "3_3") (pintype "passive"))
      (node (ref "R25") (pin "1") (pinfunction "1_1") (pintype "passive"))
    )
    (net (code "71") (name "Net-(LK3-Pad3)") (class "Default")
      (node (ref "LK3") (pin "3") (pinfunction "3_3") (pintype "passive"))
      (node (ref "R26") (pin "1") (pinfunction "1_1") (pintype "passive"))
    )
    (net (code "72") (name "Net-(LK4-Pad3)") (class "Default")
      (node (ref "LK4") (pin "3") (pinfunction "3_3") (pintype "passive"))
      (node (ref "R27") (pin "2") (pinfunction "2_2") (pintype "passive"))
    )
    (net (code "73") (name "VCC") (class "Default")
      (node (ref "C1") (pin "1") (pinfunction "1_1") (pintype "passive"))
      (node (ref "C2") (pin "1") (pinfunction "1_1") (pintype "passive"))
      (node (ref "C3") (pin "1") (pinfunction "1_1") (pintype "passive"))
      (node (ref "FS1") (pin "2") (pinfunction "2_2") (pintype "passive"))
      (node (ref "IC1") (pin "20") (pinfunction "VCC_20") (pintype "passive"))
      (node (ref "IC1") (pin "8") (pinfunction "1A3_8") (pintype "passive"))
      (node (ref "IC2") (pin "20") (pinfunction "VCC_20") (pintype "passive"))
      (node (ref "IC3") (pin "20") (pinfunction "VCC_20") (pintype "passive"))
      (node (ref "PL1") (pin "A7") (pinfunction "A7_A7") (pintype "passive"))
      (node (ref "PL1") (pin "C9") (pinfunction "C9_C9") (pintype "passive"))
      (node (ref "R11") (pin "1") (pinfunction "1_1") (pintype "passive"))
      (node (ref "R13") (pin "1") (pinfunction "1_1") (pintype "passive"))
      (node (ref "R16") (pin "2") (pinfunction "2_2") (pintype "passive"))
      (node (ref "R18") (pin "1") (pinfunction "1_1") (pintype "passive"))
      (node (ref "R2") (pin "2") (pinfunction "2_2") (pintype "passive"))
      (node (ref "R23") (pin "2") (pinfunction "2_2") (pintype "passive"))
      (node (ref "R3") (pin "1") (pinfunction "1_1") (pintype "passive"))
      (node (ref "R4") (pin "1") (pinfunction "1_1") (pintype "passive"))
      (node (ref "R5") (pin "1") (pinfunction "1_1") (pintype "passive"))
      (node (ref "R6") (pin "1") (pinfunction "1_1") (pintype "passive"))
      (node (ref "R7") (pin "1") (pinfunction "1_1") (pintype "passive"))
      (node (ref "R8") (pin "1") (pinfunction "1_1") (pintype "passive"))
      (node (ref "R9") (pin "1") (pinfunction "1_1") (pintype "passive"))
    )
    (net (code "74") (name "unconnected-(PL1-PadMH1)") (class "Default")
      (node (ref "PL1") (pin "MH1") (pinfunction "MH1_MH1") (pintype "passive+no_connect"))
    )
    (net (code "75") (name "unconnected-(PL1-PadMH2)") (class "Default")
      (node (ref "PL1") (pin "MH2") (pinfunction "MH2_MH2") (pintype "passive+no_connect"))
    )
    (net (code "76") (name "unconnected-(SK1-PadMH1)") (class "Default")
      (node (ref "SK1") (pin "MH1") (pinfunction "MH1_MH1") (pintype "passive+no_connect"))
    )
    (net (code "77") (name "unconnected-(SK1-PadMH2)") (class "Default")
      (node (ref "SK1") (pin "MH2") (pinfunction "MH2_MH2") (pintype "passive+no_connect"))
    )
  )
)
